# forcefoot.net
KiCad netlist of a schematic drawn in EAGLE
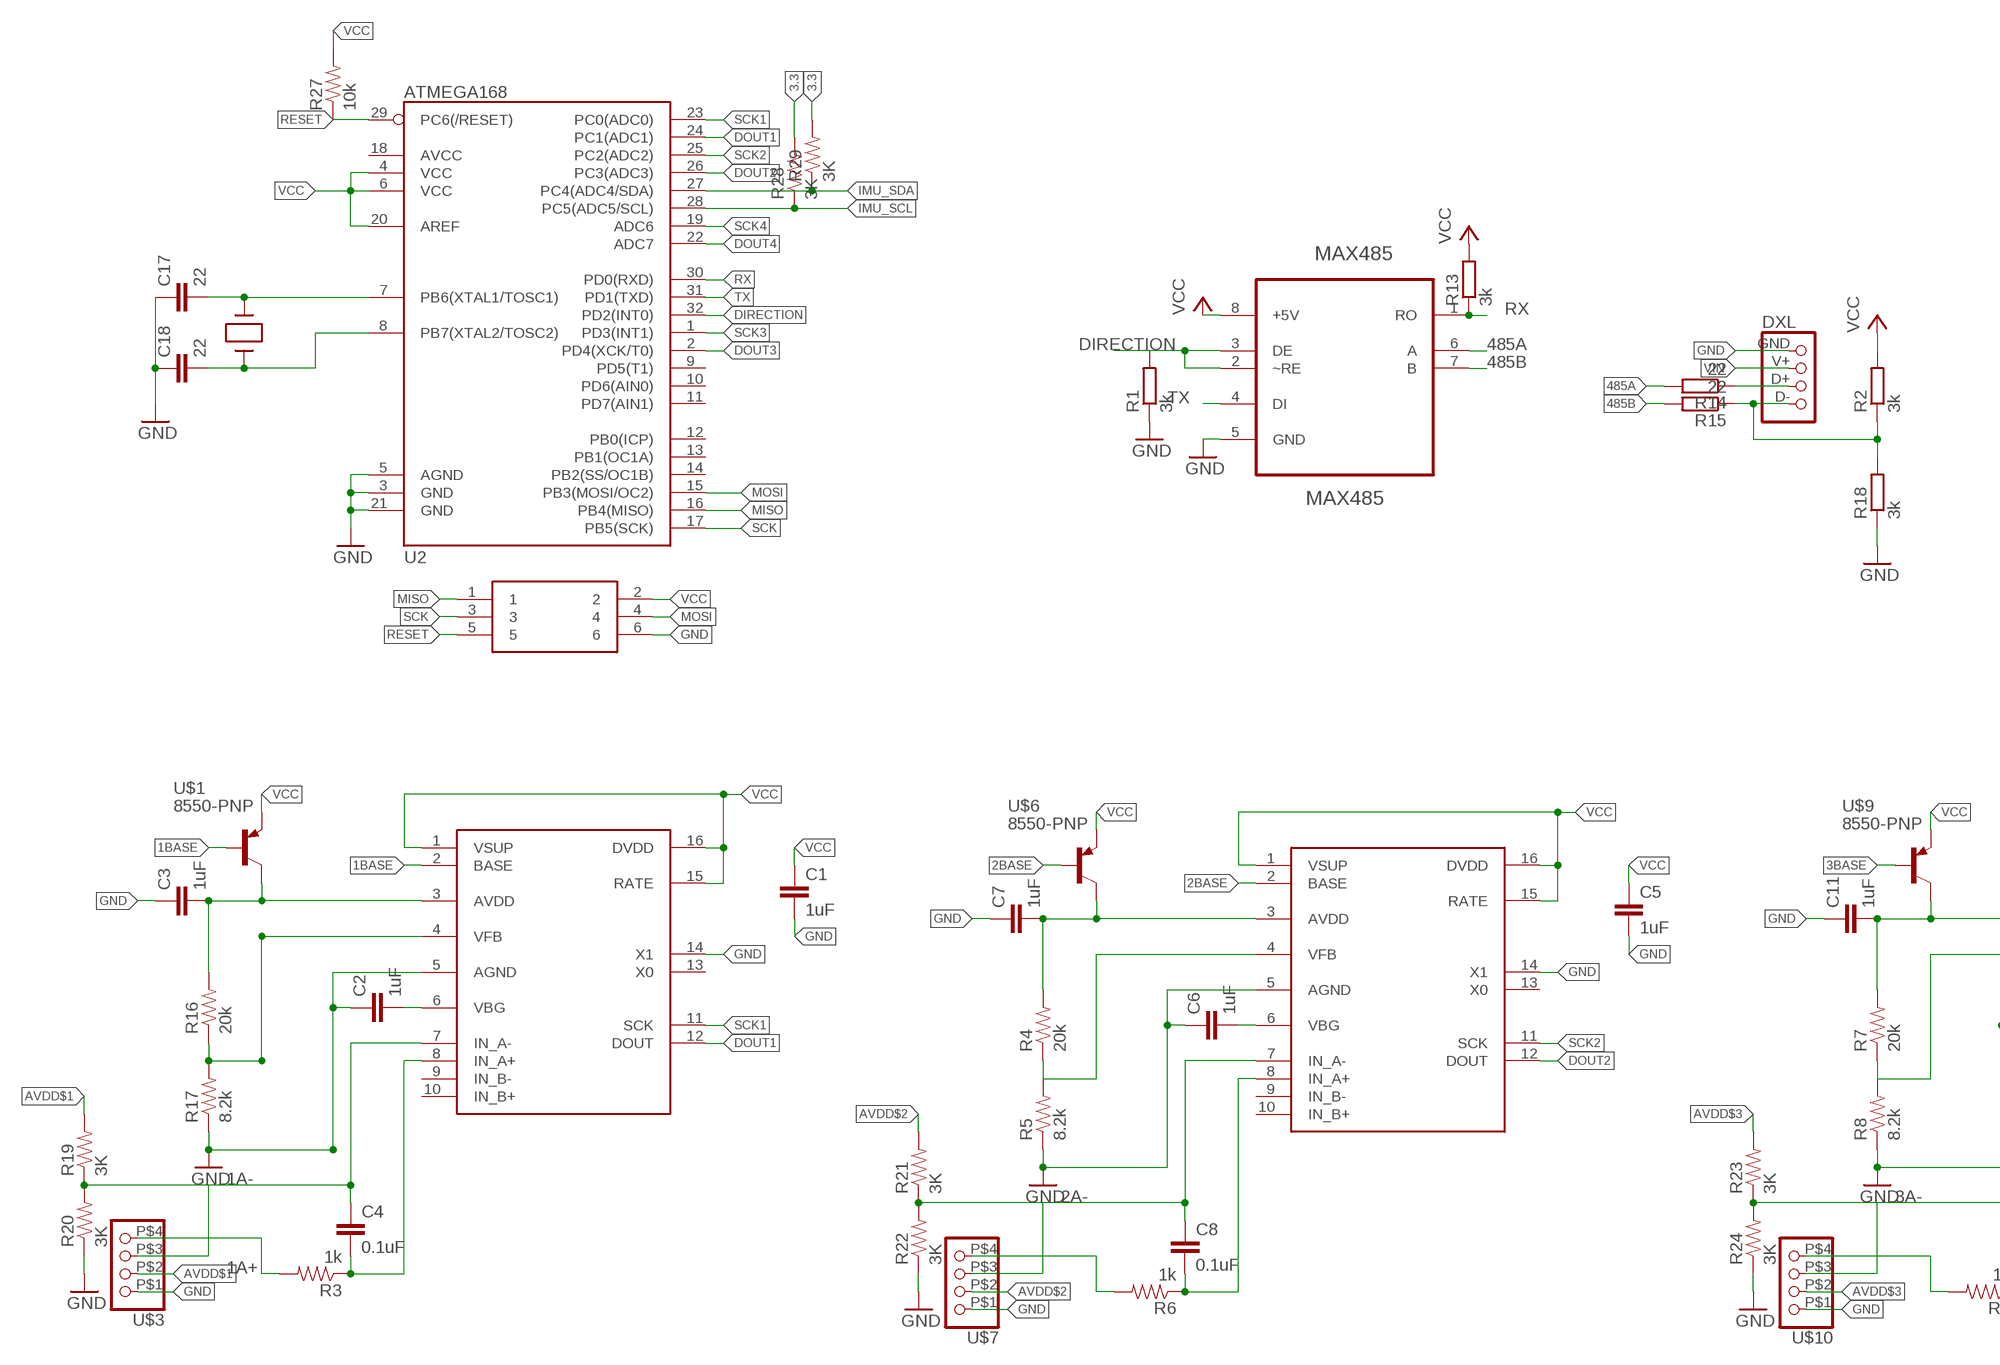
[diagram p0: schematic, sheet 1, part 1 of 2]
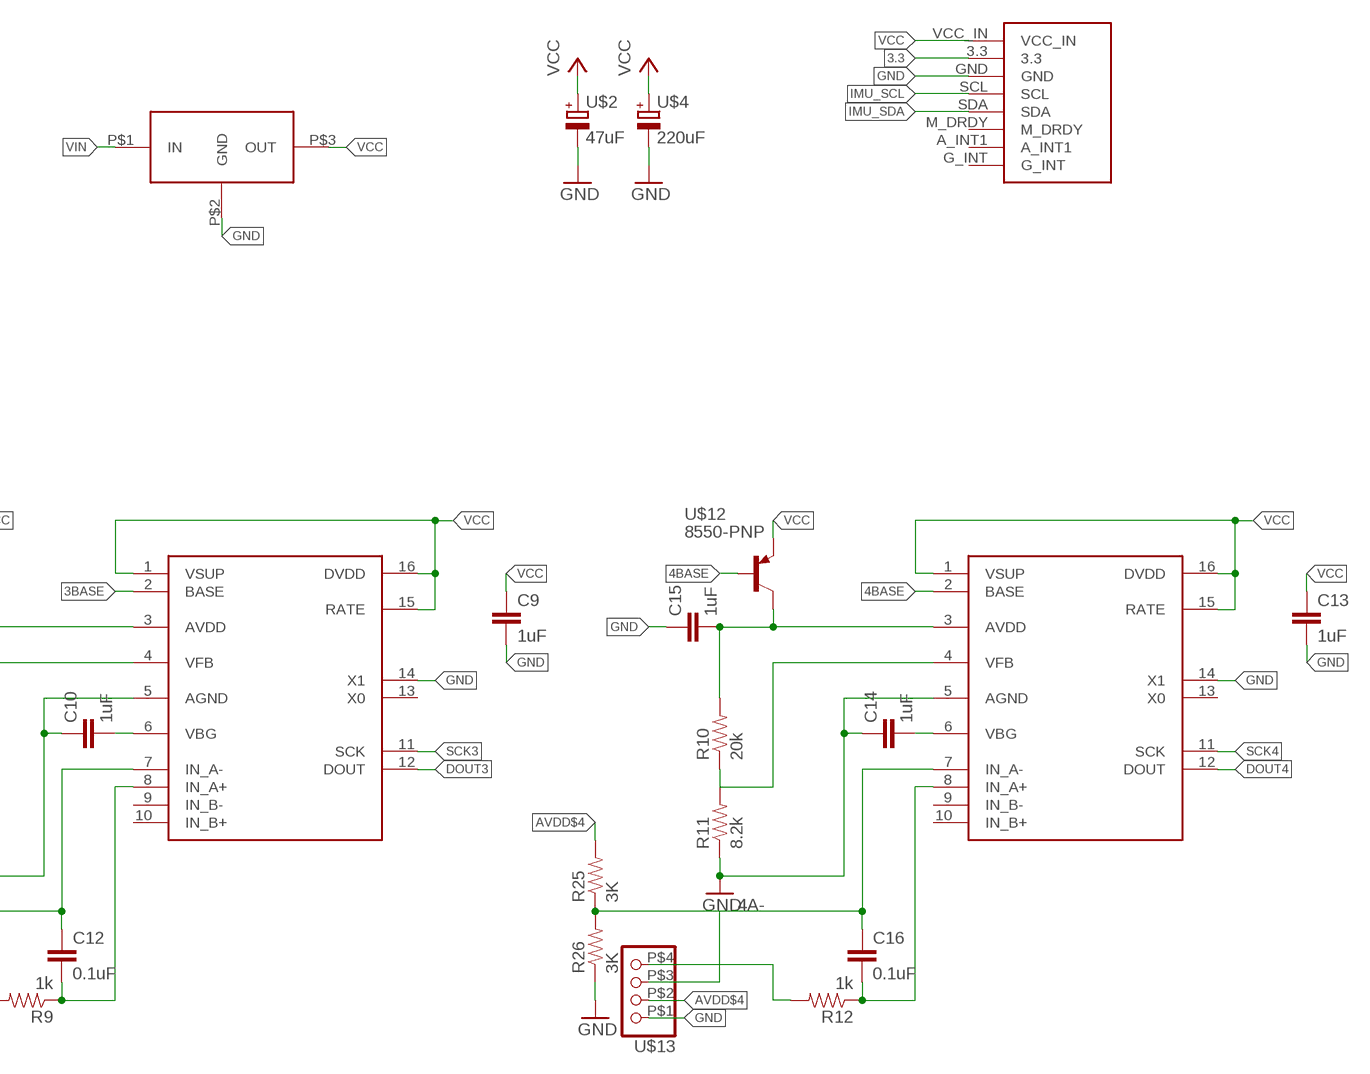
[diagram p1: schematic, sheet 1, part 2 of 2]

(export (version "E")
  (design (tool "Eeschema 10.0.6"))
  (components
    (comp (ref "C1")
      (value "1uF")
      (footprint "eagle-import:0805")
      (libsource (lib "eagle-import") (part "CAP0805"))
    )
    (comp (ref "C2")
      (value "1uF")
      (footprint "eagle-import:0805")
      (libsource (lib "eagle-import") (part "CAP0805"))
    )
    (comp (ref "C3")
      (value "1uF")
      (footprint "eagle-import:0805")
      (libsource (lib "eagle-import") (part "CAP0805"))
    )
    (comp (ref "C4")
      (value "0.1uF")
      (footprint "eagle-import:0805")
      (libsource (lib "eagle-import") (part "CAP0805"))
    )
    (comp (ref "C5")
      (value "1uF")
      (footprint "eagle-import:0805")
      (libsource (lib "eagle-import") (part "CAP0805"))
    )
    (comp (ref "C6")
      (value "1uF")
      (footprint "eagle-import:0805")
      (libsource (lib "eagle-import") (part "CAP0805"))
    )
    (comp (ref "C7")
      (value "1uF")
      (footprint "eagle-import:0805")
      (libsource (lib "eagle-import") (part "CAP0805"))
    )
    (comp (ref "C8")
      (value "0.1uF")
      (footprint "eagle-import:0805")
      (libsource (lib "eagle-import") (part "CAP0805"))
    )
    (comp (ref "C9")
      (value "1uF")
      (footprint "eagle-import:0805")
      (libsource (lib "eagle-import") (part "CAP0805"))
    )
    (comp (ref "C10")
      (value "1uF")
      (footprint "eagle-import:0805")
      (libsource (lib "eagle-import") (part "CAP0805"))
    )
    (comp (ref "C11")
      (value "1uF")
      (footprint "eagle-import:0805")
      (libsource (lib "eagle-import") (part "CAP0805"))
    )
    (comp (ref "C12")
      (value "0.1uF")
      (footprint "eagle-import:0805")
      (libsource (lib "eagle-import") (part "CAP0805"))
    )
    (comp (ref "C13")
      (value "1uF")
      (footprint "eagle-import:0805")
      (libsource (lib "eagle-import") (part "CAP0805"))
    )
    (comp (ref "C14")
      (value "1uF")
      (footprint "eagle-import:0805")
      (libsource (lib "eagle-import") (part "CAP0805"))
    )
    (comp (ref "C15")
      (value "1uF")
      (footprint "eagle-import:0805")
      (libsource (lib "eagle-import") (part "CAP0805"))
    )
    (comp (ref "C16")
      (value "0.1uF")
      (footprint "eagle-import:0805")
      (libsource (lib "eagle-import") (part "CAP0805"))
    )
    (comp (ref "C17")
      (value "22")
      (footprint "eagle-import:C0603")
      (libsource (lib "eagle-import") (part "C_EU_22PF"))
    )
    (comp (ref "C18")
      (value "22")
      (footprint "eagle-import:C0603")
      (libsource (lib "eagle-import") (part "C_EU_22PF"))
    )
    (comp (ref "DXL")
      (value "CONNEC_1X04_485")
      (footprint "eagle-import:CONNEC_485")
      (libsource (lib "eagle-import") (part "CONNEC_1X04_485"))
    )
    (comp (ref "HX1")
      (value "HX711SO16")
      (footprint "eagle-import:SO16")
      (libsource (lib "eagle-import") (part "HX711SO16"))
    )
    (comp (ref "HX2")
      (value "HX711SO16")
      (footprint "eagle-import:SO16")
      (libsource (lib "eagle-import") (part "HX711SO16"))
    )
    (comp (ref "HX3")
      (value "HX711SO16")
      (footprint "eagle-import:SO16")
      (libsource (lib "eagle-import") (part "HX711SO16"))
    )
    (comp (ref "HX4")
      (value "HX711SO16")
      (footprint "eagle-import:SO16")
      (libsource (lib "eagle-import") (part "HX711SO16"))
    )
    (comp (ref "IMU")
      (value "GY-85")
      (footprint "eagle-import:GY-85")
      (libsource (lib "eagle-import") (part "GY-85"))
    )
    (comp (ref "ISP")
      (value "CONNEC_2X03")
      (footprint "eagle-import:CONNEC_2X03")
      (libsource (lib "eagle-import") (part "CONNEC_2X03"))
    )
    (comp (ref "MAX485")
      (value "MAX485")
      (footprint "eagle-import:SO8")
      (fields (field (name "MPN") "MAX485EESA+"))
      (libsource (lib "eagle-import") (part "MAX485"))
    )
    (comp (ref "R1")
      (value "3k")
      (footprint "eagle-import:R0805")
      (libsource (lib "eagle-import") (part "RESISTANCE-R0805"))
    )
    (comp (ref "R2")
      (value "3k")
      (footprint "eagle-import:R0805")
      (libsource (lib "eagle-import") (part "RESISTANCE-R0805"))
    )
    (comp (ref "R3")
      (value "1k")
      (footprint "eagle-import:0805")
      (libsource (lib "eagle-import") (part "RESISTOR0805-RES"))
    )
    (comp (ref "R4")
      (value "20k")
      (footprint "eagle-import:0805")
      (libsource (lib "eagle-import") (part "RESISTOR0805-RES"))
    )
    (comp (ref "R5")
      (value "8.2k")
      (footprint "eagle-import:0805")
      (libsource (lib "eagle-import") (part "RESISTOR0805-RES"))
    )
    (comp (ref "R6")
      (value "1k")
      (footprint "eagle-import:0805")
      (libsource (lib "eagle-import") (part "RESISTOR0805-RES"))
    )
    (comp (ref "R7")
      (value "20k")
      (footprint "eagle-import:0805")
      (libsource (lib "eagle-import") (part "RESISTOR0805-RES"))
    )
    (comp (ref "R8")
      (value "8.2k")
      (footprint "eagle-import:0805")
      (libsource (lib "eagle-import") (part "RESISTOR0805-RES"))
    )
    (comp (ref "R9")
      (value "1k")
      (footprint "eagle-import:0805")
      (libsource (lib "eagle-import") (part "RESISTOR0805-RES"))
    )
    (comp (ref "R10")
      (value "20k")
      (footprint "eagle-import:0805")
      (libsource (lib "eagle-import") (part "RESISTOR0805-RES"))
    )
    (comp (ref "R11")
      (value "8.2k")
      (footprint "eagle-import:0805")
      (libsource (lib "eagle-import") (part "RESISTOR0805-RES"))
    )
    (comp (ref "R12")
      (value "1k")
      (footprint "eagle-import:0805")
      (libsource (lib "eagle-import") (part "RESISTOR0805-RES"))
    )
    (comp (ref "R13")
      (value "3k")
      (footprint "eagle-import:R0805")
      (libsource (lib "eagle-import") (part "RESISTANCE-R0805"))
    )
    (comp (ref "R14")
      (value "22")
      (footprint "eagle-import:R0805")
      (libsource (lib "eagle-import") (part "RESISTANCE-R0805"))
    )
    (comp (ref "R15")
      (value "22")
      (footprint "eagle-import:R0805")
      (libsource (lib "eagle-import") (part "RESISTANCE-R0805"))
    )
    (comp (ref "R16")
      (value "20k")
      (footprint "eagle-import:0805")
      (libsource (lib "eagle-import") (part "RESISTOR0805-RES"))
    )
    (comp (ref "R17")
      (value "8.2k")
      (footprint "eagle-import:0805")
      (libsource (lib "eagle-import") (part "RESISTOR0805-RES"))
    )
    (comp (ref "R18")
      (value "3k")
      (footprint "eagle-import:R0805")
      (libsource (lib "eagle-import") (part "RESISTANCE-R0805"))
    )
    (comp (ref "R19")
      (value "3K")
      (footprint "eagle-import:0805")
      (libsource (lib "eagle-import") (part "RESISTOR0805-RES"))
    )
    (comp (ref "R20")
      (value "3K")
      (footprint "eagle-import:0805")
      (libsource (lib "eagle-import") (part "RESISTOR0805-RES"))
    )
    (comp (ref "R21")
      (value "3K")
      (footprint "eagle-import:0805")
      (libsource (lib "eagle-import") (part "RESISTOR0805-RES"))
    )
    (comp (ref "R22")
      (value "3K")
      (footprint "eagle-import:0805")
      (libsource (lib "eagle-import") (part "RESISTOR0805-RES"))
    )
    (comp (ref "R23")
      (value "3K")
      (footprint "eagle-import:0805")
      (libsource (lib "eagle-import") (part "RESISTOR0805-RES"))
    )
    (comp (ref "R24")
      (value "3K")
      (footprint "eagle-import:0805")
      (libsource (lib "eagle-import") (part "RESISTOR0805-RES"))
    )
    (comp (ref "R25")
      (value "3K")
      (footprint "eagle-import:0805")
      (libsource (lib "eagle-import") (part "RESISTOR0805-RES"))
    )
    (comp (ref "R26")
      (value "3K")
      (footprint "eagle-import:0805")
      (libsource (lib "eagle-import") (part "RESISTOR0805-RES"))
    )
    (comp (ref "R27")
      (value "10k")
      (footprint "eagle-import:0805")
      (libsource (lib "eagle-import") (part "RESISTOR0805-RES"))
    )
    (comp (ref "R28")
      (value "3K")
      (footprint "eagle-import:0805")
      (libsource (lib "eagle-import") (part "RESISTOR0805-RES"))
    )
    (comp (ref "R29")
      (value "3K")
      (footprint "eagle-import:0805")
      (libsource (lib "eagle-import") (part "RESISTOR0805-RES"))
    )
    (comp (ref "REG")
      (value "REG_5V")
      (footprint "eagle-import:TRACOPOWER")
      (libsource (lib "eagle-import") (part "REG_5V"))
    )
    (comp (ref "U$1")
      (value "8550-PNP")
      (footprint "eagle-import:SOT-23")
      (libsource (lib "eagle-import") (part "8550-PNP"))
    )
    (comp (ref "U$2")
      (value "47uF")
      (footprint "eagle-import:PANASONIC_D")
      (libsource (lib "eagle-import") (part "CPOL_EUPANASONIC_D"))
    )
    (comp (ref "U$3")
      (value "CONNEC_1X041.5")
      (footprint "eagle-import:4P1.5")
      (libsource (lib "eagle-import") (part "CONNEC_1X041.5"))
    )
    (comp (ref "U$4")
      (value "220uF")
      (footprint "eagle-import:PANASONIC_D8")
      (libsource (lib "eagle-import") (part "CPOL_EUPANASONIC_D8"))
    )
    (comp (ref "U$6")
      (value "8550-PNP")
      (footprint "eagle-import:SOT-23")
      (libsource (lib "eagle-import") (part "8550-PNP"))
    )
    (comp (ref "U$7")
      (value "CONNEC_1X041.5")
      (footprint "eagle-import:4P1.5")
      (libsource (lib "eagle-import") (part "CONNEC_1X041.5"))
    )
    (comp (ref "U$9")
      (value "8550-PNP")
      (footprint "eagle-import:SOT-23")
      (libsource (lib "eagle-import") (part "8550-PNP"))
    )
    (comp (ref "U$10")
      (value "CONNEC_1X041.5")
      (footprint "eagle-import:4P1.5")
      (libsource (lib "eagle-import") (part "CONNEC_1X041.5"))
    )
    (comp (ref "U$12")
      (value "8550-PNP")
      (footprint "eagle-import:SOT-23")
      (libsource (lib "eagle-import") (part "8550-PNP"))
    )
    (comp (ref "U$13")
      (value "CONNEC_1X041.5")
      (footprint "eagle-import:4P1.5")
      (libsource (lib "eagle-import") (part "CONNEC_1X041.5"))
    )
    (comp (ref "U2")
      (value "ATMEGA168")
      (footprint "eagle-import:TQFP32-08")
      (libsource (lib "eagle-import") (part "ATMEGA168"))
    )
    (comp (ref "XTAL1")
      (value "QUARTZ")
      (footprint "eagle-import:HC49US")
      (libsource (lib "eagle-import") (part "QUARTZ"))
    )
  )
  (nets
    (net (code "1") (name "/1A+") (class "Default")
      (node (ref "R3") (pin "2") (pinfunction "2_2") (pintype "passive"))
      (node (ref "U$3") (pin "P$4") (pinfunction "4_P$4") (pintype "passive"))
    )
    (net (code "2") (name "/1A-") (class "Default")
      (node (ref "C4") (pin "1") (pinfunction "1_1") (pintype "passive"))
      (node (ref "HX1") (pin "7") (pinfunction "IN_A-_7") (pintype "bidirectional"))
      (node (ref "R19") (pin "1") (pinfunction "1_1") (pintype "passive"))
      (node (ref "R20") (pin "2") (pinfunction "2_2") (pintype "passive"))
      (node (ref "U$3") (pin "P$3") (pinfunction "3_P$3") (pintype "passive"))
    )
    (net (code "3") (name "/2A-") (class "Default")
      (node (ref "C8") (pin "1") (pinfunction "1_1") (pintype "passive"))
      (node (ref "HX2") (pin "7") (pinfunction "IN_A-_7") (pintype "bidirectional"))
      (node (ref "R21") (pin "1") (pinfunction "1_1") (pintype "passive"))
      (node (ref "R22") (pin "2") (pinfunction "2_2") (pintype "passive"))
      (node (ref "U$7") (pin "P$3") (pinfunction "3_P$3") (pintype "passive"))
    )
    (net (code "4") (name "/3A-") (class "Default")
      (node (ref "C12") (pin "1") (pinfunction "1_1") (pintype "passive"))
      (node (ref "HX3") (pin "7") (pinfunction "IN_A-_7") (pintype "bidirectional"))
      (node (ref "R23") (pin "1") (pinfunction "1_1") (pintype "passive"))
      (node (ref "R24") (pin "2") (pinfunction "2_2") (pintype "passive"))
      (node (ref "U$10") (pin "P$3") (pinfunction "3_P$3") (pintype "passive"))
    )
    (net (code "5") (name "/4A-") (class "Default")
      (node (ref "C16") (pin "1") (pinfunction "1_1") (pintype "passive"))
      (node (ref "HX4") (pin "7") (pinfunction "IN_A-_7") (pintype "bidirectional"))
      (node (ref "R25") (pin "1") (pinfunction "1_1") (pintype "passive"))
      (node (ref "R26") (pin "2") (pinfunction "2_2") (pintype "passive"))
      (node (ref "U$13") (pin "P$3") (pinfunction "3_P$3") (pintype "passive"))
    )
    (net (code "6") (name "1BASE") (class "Default")
      (node (ref "HX1") (pin "2") (pinfunction "BASE_2") (pintype "bidirectional"))
      (node (ref "U$1") (pin "1") (pinfunction "B_1") (pintype "passive"))
    )
    (net (code "7") (name "2BASE") (class "Default")
      (node (ref "HX2") (pin "2") (pinfunction "BASE_2") (pintype "bidirectional"))
      (node (ref "U$6") (pin "1") (pinfunction "B_1") (pintype "passive"))
    )
    (net (code "8") (name "3.3") (class "Default")
      (node (ref "IMU") (pin "3.3") (pinfunction "3.3_3.3") (pintype "bidirectional"))
      (node (ref "R28") (pin "2") (pinfunction "2_2") (pintype "passive"))
      (node (ref "R29") (pin "2") (pinfunction "2_2") (pintype "passive"))
    )
    (net (code "9") (name "3BASE") (class "Default")
      (node (ref "HX3") (pin "2") (pinfunction "BASE_2") (pintype "bidirectional"))
      (node (ref "U$9") (pin "1") (pinfunction "B_1") (pintype "passive"))
    )
    (net (code "10") (name "4BASE") (class "Default")
      (node (ref "HX4") (pin "2") (pinfunction "BASE_2") (pintype "bidirectional"))
      (node (ref "U$12") (pin "1") (pinfunction "B_1") (pintype "passive"))
    )
    (net (code "11") (name "485A") (class "Default")
      (node (ref "MAX485") (pin "6") (pinfunction "A_6") (pintype "bidirectional"))
      (node (ref "R14") (pin "2") (pinfunction "2_2") (pintype "passive"))
    )
    (net (code "12") (name "485B") (class "Default")
      (node (ref "MAX485") (pin "7") (pinfunction "B_7") (pintype "bidirectional"))
      (node (ref "R15") (pin "2") (pinfunction "2_2") (pintype "passive"))
    )
    (net (code "13") (name "AVDD$1") (class "Default")
      (node (ref "C3") (pin "2") (pinfunction "2_2") (pintype "passive"))
      (node (ref "HX1") (pin "3") (pinfunction "AVDD_3") (pintype "bidirectional"))
      (node (ref "R16") (pin "2") (pinfunction "2_2") (pintype "passive"))
      (node (ref "R19") (pin "2") (pinfunction "2_2") (pintype "passive"))
      (node (ref "U$1") (pin "3") (pinfunction "C_3") (pintype "passive"))
      (node (ref "U$3") (pin "P$2") (pinfunction "2_P$2") (pintype "passive"))
    )
    (net (code "14") (name "AVDD$2") (class "Default")
      (node (ref "C7") (pin "2") (pinfunction "2_2") (pintype "passive"))
      (node (ref "HX2") (pin "3") (pinfunction "AVDD_3") (pintype "bidirectional"))
      (node (ref "R21") (pin "2") (pinfunction "2_2") (pintype "passive"))
      (node (ref "R4") (pin "2") (pinfunction "2_2") (pintype "passive"))
      (node (ref "U$6") (pin "3") (pinfunction "C_3") (pintype "passive"))
      (node (ref "U$7") (pin "P$2") (pinfunction "2_P$2") (pintype "passive"))
    )
    (net (code "15") (name "AVDD$3") (class "Default")
      (node (ref "C11") (pin "2") (pinfunction "2_2") (pintype "passive"))
      (node (ref "HX3") (pin "3") (pinfunction "AVDD_3") (pintype "bidirectional"))
      (node (ref "R23") (pin "2") (pinfunction "2_2") (pintype "passive"))
      (node (ref "R7") (pin "2") (pinfunction "2_2") (pintype "passive"))
      (node (ref "U$10") (pin "P$2") (pinfunction "2_P$2") (pintype "passive"))
      (node (ref "U$9") (pin "3") (pinfunction "C_3") (pintype "passive"))
    )
    (net (code "16") (name "AVDD$4") (class "Default")
      (node (ref "C15") (pin "2") (pinfunction "2_2") (pintype "passive"))
      (node (ref "HX4") (pin "3") (pinfunction "AVDD_3") (pintype "bidirectional"))
      (node (ref "R10") (pin "2") (pinfunction "2_2") (pintype "passive"))
      (node (ref "R25") (pin "2") (pinfunction "2_2") (pintype "passive"))
      (node (ref "U$12") (pin "3") (pinfunction "C_3") (pintype "passive"))
      (node (ref "U$13") (pin "P$2") (pinfunction "2_P$2") (pintype "passive"))
    )
    (net (code "17") (name "DIRECTION") (class "Default")
      (node (ref "MAX485") (pin "2") (pinfunction "~{RE}_2") (pintype "input"))
      (node (ref "MAX485") (pin "3") (pinfunction "DE_3") (pintype "input"))
      (node (ref "R1") (pin "2") (pinfunction "2_2") (pintype "passive"))
      (node (ref "U2") (pin "32") (pinfunction "PD2(INT0)_32") (pintype "bidirectional"))
    )
    (net (code "18") (name "DOUT1") (class "Default")
      (node (ref "HX1") (pin "12") (pinfunction "DOUT_12") (pintype "bidirectional"))
      (node (ref "U2") (pin "24") (pinfunction "PC1(ADC1)_24") (pintype "bidirectional"))
    )
    (net (code "19") (name "DOUT2") (class "Default")
      (node (ref "HX2") (pin "12") (pinfunction "DOUT_12") (pintype "bidirectional"))
      (node (ref "U2") (pin "26") (pinfunction "PC3(ADC3)_26") (pintype "bidirectional"))
    )
    (net (code "20") (name "DOUT3") (class "Default")
      (node (ref "HX3") (pin "12") (pinfunction "DOUT_12") (pintype "bidirectional"))
      (node (ref "U2") (pin "2") (pinfunction "PD4(XCK/T0)_2") (pintype "bidirectional"))
    )
    (net (code "21") (name "DOUT4") (class "Default")
      (node (ref "HX4") (pin "12") (pinfunction "DOUT_12") (pintype "bidirectional"))
      (node (ref "U2") (pin "22") (pinfunction "ADC7_22") (pintype "bidirectional"))
    )
    (net (code "22") (name "GND") (class "Default")
      (node (ref "C1") (pin "2") (pinfunction "2_2") (pintype "passive"))
      (node (ref "C10") (pin "1") (pinfunction "1_1") (pintype "passive"))
      (node (ref "C11") (pin "1") (pinfunction "1_1") (pintype "passive"))
      (node (ref "C13") (pin "2") (pinfunction "2_2") (pintype "passive"))
      (node (ref "C14") (pin "1") (pinfunction "1_1") (pintype "passive"))
      (node (ref "C15") (pin "1") (pinfunction "1_1") (pintype "passive"))
      (node (ref "C17") (pin "1") (pinfunction "1_1") (pintype "passive"))
      (node (ref "C18") (pin "1") (pinfunction "1_1") (pintype "passive"))
      (node (ref "C2") (pin "1") (pinfunction "1_1") (pintype "passive"))
      (node (ref "C3") (pin "1") (pinfunction "1_1") (pintype "passive"))
      (node (ref "C5") (pin "2") (pinfunction "2_2") (pintype "passive"))
      (node (ref "C6") (pin "1") (pinfunction "1_1") (pintype "passive"))
      (node (ref "C7") (pin "1") (pinfunction "1_1") (pintype "passive"))
      (node (ref "C9") (pin "2") (pinfunction "2_2") (pintype "passive"))
      (node (ref "DXL") (pin "GND") (pinfunction "1_GND") (pintype "passive"))
      (node (ref "HX1") (pin "14") (pinfunction "X1_14") (pintype "bidirectional"))
      (node (ref "HX1") (pin "5") (pinfunction "AGND_5") (pintype "bidirectional"))
      (node (ref "HX2") (pin "14") (pinfunction "X1_14") (pintype "bidirectional"))
      (node (ref "HX2") (pin "5") (pinfunction "AGND_5") (pintype "bidirectional"))
      (node (ref "HX3") (pin "14") (pinfunction "X1_14") (pintype "bidirectional"))
      (node (ref "HX3") (pin "5") (pinfunction "AGND_5") (pintype "bidirectional"))
      (node (ref "HX4") (pin "14") (pinfunction "X1_14") (pintype "bidirectional"))
      (node (ref "HX4") (pin "5") (pinfunction "AGND_5") (pintype "bidirectional"))
      (node (ref "IMU") (pin "GND") (pinfunction "GND_GND") (pintype "bidirectional"))
      (node (ref "ISP") (pin "6") (pinfunction "6_6") (pintype "bidirectional"))
      (node (ref "MAX485") (pin "5") (pinfunction "GND_5") (pintype "passive"))
      (node (ref "R1") (pin "1") (pinfunction "1_1") (pintype "passive"))
      (node (ref "R11") (pin "1") (pinfunction "1_1") (pintype "passive"))
      (node (ref "R17") (pin "1") (pinfunction "1_1") (pintype "passive"))
      (node (ref "R18") (pin "1") (pinfunction "1_1") (pintype "passive"))
      (node (ref "R20") (pin "1") (pinfunction "1_1") (pintype "passive"))
      (node (ref "R22") (pin "1") (pinfunction "1_1") (pintype "passive"))
      (node (ref "R24") (pin "1") (pinfunction "1_1") (pintype "passive"))
      (node (ref "R26") (pin "1") (pinfunction "1_1") (pintype "passive"))
      (node (ref "R5") (pin "1") (pinfunction "1_1") (pintype "passive"))
      (node (ref "R8") (pin "1") (pinfunction "1_1") (pintype "passive"))
      (node (ref "REG") (pin "P$2") (pinfunction "GND_P$2") (pintype "bidirectional"))
      (node (ref "U$10") (pin "P$1") (pinfunction "1_P$1") (pintype "passive"))
      (node (ref "U$13") (pin "P$1") (pinfunction "1_P$1") (pintype "passive"))
      (node (ref "U$2") (pin "-") (pinfunction "-_-") (pintype "passive"))
      (node (ref "U$3") (pin "P$1") (pinfunction "1_P$1") (pintype "passive"))
      (node (ref "U$4") (pin "-") (pinfunction "-_-") (pintype "passive"))
      (node (ref "U$7") (pin "P$1") (pinfunction "1_P$1") (pintype "passive"))
      (node (ref "U2") (pin "21") (pinfunction "GND_21") (pintype "bidirectional"))
      (node (ref "U2") (pin "3") (pinfunction "GND_3") (pintype "bidirectional"))
      (node (ref "U2") (pin "5") (pinfunction "AGND_5") (pintype "bidirectional"))
    )
    (net (code "23") (name "IMU_SCL") (class "Default")
      (node (ref "IMU") (pin "SCL") (pinfunction "SCL_SCL") (pintype "bidirectional"))
      (node (ref "R28") (pin "1") (pinfunction "1_1") (pintype "passive"))
      (node (ref "U2") (pin "28") (pinfunction "PC5(ADC5/SCL)_28") (pintype "bidirectional"))
    )
    (net (code "24") (name "IMU_SDA") (class "Default")
      (node (ref "IMU") (pin "SDA") (pinfunction "SDA_SDA") (pintype "bidirectional"))
      (node (ref "R29") (pin "1") (pinfunction "1_1") (pintype "passive"))
      (node (ref "U2") (pin "27") (pinfunction "PC4(ADC4/SDA)_27") (pintype "bidirectional"))
    )
    (net (code "25") (name "MISO") (class "Default")
      (node (ref "ISP") (pin "1") (pinfunction "1_1") (pintype "bidirectional"))
      (node (ref "U2") (pin "16") (pinfunction "PB4(MISO)_16") (pintype "bidirectional"))
    )
    (net (code "26") (name "MOSI") (class "Default")
      (node (ref "ISP") (pin "4") (pinfunction "4_4") (pintype "bidirectional"))
      (node (ref "U2") (pin "15") (pinfunction "PB3(MOSI/OC2)_15") (pintype "bidirectional"))
    )
    (net (code "27") (name "Net-(DXL-3)") (class "Default")
      (node (ref "DXL") (pin "D+") (pinfunction "3_D+") (pintype "passive"))
      (node (ref "R14") (pin "1") (pinfunction "1_1") (pintype "passive"))
    )
    (net (code "28") (name "Net-(DXL-4)") (class "Default")
      (node (ref "DXL") (pin "D-") (pinfunction "4_D-") (pintype "passive"))
      (node (ref "R15") (pin "1") (pinfunction "1_1") (pintype "passive"))
      (node (ref "R18") (pin "2") (pinfunction "2_2") (pintype "passive"))
      (node (ref "R2") (pin "1") (pinfunction "1_1") (pintype "passive"))
    )
    (net (code "29") (name "Net-(HX1-IN_A+)") (class "Default")
      (node (ref "C4") (pin "2") (pinfunction "2_2") (pintype "passive"))
      (node (ref "HX1") (pin "8") (pinfunction "IN_A+_8") (pintype "bidirectional"))
      (node (ref "R3") (pin "1") (pinfunction "1_1") (pintype "passive"))
    )
    (net (code "30") (name "Net-(HX1-VBG)") (class "Default")
      (node (ref "C2") (pin "2") (pinfunction "2_2") (pintype "passive"))
      (node (ref "HX1") (pin "6") (pinfunction "VBG_6") (pintype "bidirectional"))
    )
    (net (code "31") (name "Net-(HX1-VFB)") (class "Default")
      (node (ref "HX1") (pin "4") (pinfunction "VFB_4") (pintype "bidirectional"))
      (node (ref "R16") (pin "1") (pinfunction "1_1") (pintype "passive"))
      (node (ref "R17") (pin "2") (pinfunction "2_2") (pintype "passive"))
    )
    (net (code "32") (name "Net-(HX2-IN_A+)") (class "Default")
      (node (ref "C8") (pin "2") (pinfunction "2_2") (pintype "passive"))
      (node (ref "HX2") (pin "8") (pinfunction "IN_A+_8") (pintype "bidirectional"))
      (node (ref "R6") (pin "1") (pinfunction "1_1") (pintype "passive"))
    )
    (net (code "33") (name "Net-(HX2-VBG)") (class "Default")
      (node (ref "C6") (pin "2") (pinfunction "2_2") (pintype "passive"))
      (node (ref "HX2") (pin "6") (pinfunction "VBG_6") (pintype "bidirectional"))
    )
    (net (code "34") (name "Net-(HX2-VFB)") (class "Default")
      (node (ref "HX2") (pin "4") (pinfunction "VFB_4") (pintype "bidirectional"))
      (node (ref "R4") (pin "1") (pinfunction "1_1") (pintype "passive"))
      (node (ref "R5") (pin "2") (pinfunction "2_2") (pintype "passive"))
    )
    (net (code "35") (name "Net-(HX3-IN_A+)") (class "Default")
      (node (ref "C12") (pin "2") (pinfunction "2_2") (pintype "passive"))
      (node (ref "HX3") (pin "8") (pinfunction "IN_A+_8") (pintype "bidirectional"))
      (node (ref "R9") (pin "1") (pinfunction "1_1") (pintype "passive"))
    )
    (net (code "36") (name "Net-(HX3-VBG)") (class "Default")
      (node (ref "C10") (pin "2") (pinfunction "2_2") (pintype "passive"))
      (node (ref "HX3") (pin "6") (pinfunction "VBG_6") (pintype "bidirectional"))
    )
    (net (code "37") (name "Net-(HX3-VFB)") (class "Default")
      (node (ref "HX3") (pin "4") (pinfunction "VFB_4") (pintype "bidirectional"))
      (node (ref "R7") (pin "1") (pinfunction "1_1") (pintype "passive"))
      (node (ref "R8") (pin "2") (pinfunction "2_2") (pintype "passive"))
    )
    (net (code "38") (name "Net-(HX4-IN_A+)") (class "Default")
      (node (ref "C16") (pin "2") (pinfunction "2_2") (pintype "passive"))
      (node (ref "HX4") (pin "8") (pinfunction "IN_A+_8") (pintype "bidirectional"))
      (node (ref "R12") (pin "1") (pinfunction "1_1") (pintype "passive"))
    )
    (net (code "39") (name "Net-(HX4-VBG)") (class "Default")
      (node (ref "C14") (pin "2") (pinfunction "2_2") (pintype "passive"))
      (node (ref "HX4") (pin "6") (pinfunction "VBG_6") (pintype "bidirectional"))
    )
    (net (code "40") (name "Net-(HX4-VFB)") (class "Default")
      (node (ref "HX4") (pin "4") (pinfunction "VFB_4") (pintype "bidirectional"))
      (node (ref "R10") (pin "1") (pinfunction "1_1") (pintype "passive"))
      (node (ref "R11") (pin "2") (pinfunction "2_2") (pintype "passive"))
    )
    (net (code "41") (name "Net-(U$7-4)") (class "Default")
      (node (ref "R6") (pin "2") (pinfunction "2_2") (pintype "passive"))
      (node (ref "U$7") (pin "P$4") (pinfunction "4_P$4") (pintype "passive"))
    )
    (net (code "42") (name "Net-(U$10-4)") (class "Default")
      (node (ref "R9") (pin "2") (pinfunction "2_2") (pintype "passive"))
      (node (ref "U$10") (pin "P$4") (pinfunction "4_P$4") (pintype "passive"))
    )
    (net (code "43") (name "Net-(U$13-4)") (class "Default")
      (node (ref "R12") (pin "2") (pinfunction "2_2") (pintype "passive"))
      (node (ref "U$13") (pin "P$4") (pinfunction "4_P$4") (pintype "passive"))
    )
    (net (code "44") (name "Net-(U2-PB6(XTAL1{slash}TOSC1))") (class "Default")
      (node (ref "C17") (pin "2") (pinfunction "2_2") (pintype "passive"))
      (node (ref "U2") (pin "7") (pinfunction "PB6(XTAL1/TOSC1)_7") (pintype "bidirectional"))
      (node (ref "XTAL1") (pin "2") (pinfunction "2_2") (pintype "bidirectional"))
    )
    (net (code "45") (name "Net-(U2-PB7(XTAL2{slash}TOSC2))") (class "Default")
      (node (ref "C18") (pin "2") (pinfunction "2_2") (pintype "passive"))
      (node (ref "U2") (pin "8") (pinfunction "PB7(XTAL2/TOSC2)_8") (pintype "bidirectional"))
      (node (ref "XTAL1") (pin "1") (pinfunction "1_1") (pintype "bidirectional"))
    )
    (net (code "46") (name "RESET") (class "Default")
      (node (ref "ISP") (pin "5") (pinfunction "5_5") (pintype "bidirectional"))
      (node (ref "R27") (pin "1") (pinfunction "1_1") (pintype "passive"))
      (node (ref "U2") (pin "29") (pinfunction "PC6(/RESET)_29") (pintype "bidirectional"))
    )
    (net (code "47") (name "RX") (class "Default")
      (node (ref "MAX485") (pin "1") (pinfunction "RO_1") (pintype "output"))
      (node (ref "R13") (pin "1") (pinfunction "1_1") (pintype "passive"))
      (node (ref "U2") (pin "30") (pinfunction "PD0(RXD)_30") (pintype "bidirectional"))
    )
    (net (code "48") (name "SCK") (class "Default")
      (node (ref "ISP") (pin "3") (pinfunction "3_3") (pintype "bidirectional"))
      (node (ref "U2") (pin "17") (pinfunction "PB5(SCK)_17") (pintype "bidirectional"))
    )
    (net (code "49") (name "SCK1") (class "Default")
      (node (ref "HX1") (pin "11") (pinfunction "SCK_11") (pintype "bidirectional"))
      (node (ref "U2") (pin "23") (pinfunction "PC0(ADC0)_23") (pintype "bidirectional"))
    )
    (net (code "50") (name "SCK2") (class "Default")
      (node (ref "HX2") (pin "11") (pinfunction "SCK_11") (pintype "bidirectional"))
      (node (ref "U2") (pin "25") (pinfunction "PC2(ADC2)_25") (pintype "bidirectional"))
    )
    (net (code "51") (name "SCK3") (class "Default")
      (node (ref "HX3") (pin "11") (pinfunction "SCK_11") (pintype "bidirectional"))
      (node (ref "U2") (pin "1") (pinfunction "PD3(INT1)_1") (pintype "bidirectional"))
    )
    (net (code "52") (name "SCK4") (class "Default")
      (node (ref "HX4") (pin "11") (pinfunction "SCK_11") (pintype "bidirectional"))
      (node (ref "U2") (pin "19") (pinfunction "ADC6_19") (pintype "bidirectional"))
    )
    (net (code "53") (name "TX") (class "Default")
      (node (ref "MAX485") (pin "4") (pinfunction "DI_4") (pintype "input"))
      (node (ref "U2") (pin "31") (pinfunction "PD1(TXD)_31") (pintype "bidirectional"))
    )
    (net (code "54") (name "VCC") (class "Default")
      (node (ref "C1") (pin "1") (pinfunction "1_1") (pintype "passive"))
      (node (ref "C13") (pin "1") (pinfunction "1_1") (pintype "passive"))
      (node (ref "C5") (pin "1") (pinfunction "1_1") (pintype "passive"))
      (node (ref "C9") (pin "1") (pinfunction "1_1") (pintype "passive"))
      (node (ref "HX1") (pin "1") (pinfunction "VSUP_1") (pintype "bidirectional"))
      (node (ref "HX1") (pin "15") (pinfunction "RATE_15") (pintype "bidirectional"))
      (node (ref "HX1") (pin "16") (pinfunction "DVDD_16") (pintype "bidirectional"))
      (node (ref "HX2") (pin "1") (pinfunction "VSUP_1") (pintype "bidirectional"))
      (node (ref "HX2") (pin "15") (pinfunction "RATE_15") (pintype "bidirectional"))
      (node (ref "HX2") (pin "16") (pinfunction "DVDD_16") (pintype "bidirectional"))
      (node (ref "HX3") (pin "1") (pinfunction "VSUP_1") (pintype "bidirectional"))
      (node (ref "HX3") (pin "15") (pinfunction "RATE_15") (pintype "bidirectional"))
      (node (ref "HX3") (pin "16") (pinfunction "DVDD_16") (pintype "bidirectional"))
      (node (ref "HX4") (pin "1") (pinfunction "VSUP_1") (pintype "bidirectional"))
      (node (ref "HX4") (pin "15") (pinfunction "RATE_15") (pintype "bidirectional"))
      (node (ref "HX4") (pin "16") (pinfunction "DVDD_16") (pintype "bidirectional"))
      (node (ref "IMU") (pin "VCC_IN") (pinfunction "VCC_IN_VCC_IN") (pintype "bidirectional"))
      (node (ref "ISP") (pin "2") (pinfunction "2_2") (pintype "bidirectional"))
      (node (ref "MAX485") (pin "8") (pinfunction "+5V_8") (pintype "power_in"))
      (node (ref "R13") (pin "2") (pinfunction "2_2") (pintype "passive"))
      (node (ref "R2") (pin "2") (pinfunction "2_2") (pintype "passive"))
      (node (ref "R27") (pin "2") (pinfunction "2_2") (pintype "passive"))
      (node (ref "REG") (pin "P$3") (pinfunction "OUT_P$3") (pintype "bidirectional"))
      (node (ref "U$1") (pin "2") (pinfunction "E_2") (pintype "passive"))
      (node (ref "U$12") (pin "2") (pinfunction "E_2") (pintype "passive"))
      (node (ref "U$2") (pin "+") (pinfunction "+_+") (pintype "passive"))
      (node (ref "U$4") (pin "+") (pinfunction "+_+") (pintype "passive"))
      (node (ref "U$6") (pin "2") (pinfunction "E_2") (pintype "passive"))
      (node (ref "U$9") (pin "2") (pinfunction "E_2") (pintype "passive"))
      (node (ref "U2") (pin "20") (pinfunction "AREF_20") (pintype "bidirectional"))
      (node (ref "U2") (pin "4") (pinfunction "VCC_4") (pintype "bidirectional"))
      (node (ref "U2") (pin "6") (pinfunction "VCC_6") (pintype "bidirectional"))
    )
    (net (code "55") (name "VIN") (class "Default")
      (node (ref "DXL") (pin "V+") (pinfunction "2_V+") (pintype "passive"))
      (node (ref "REG") (pin "P$1") (pinfunction "IN_P$1") (pintype "bidirectional"))
    )
    (net (code "56") (name "unconnected-(HX1-IN_B+-Pad10)") (class "Default")
      (node (ref "HX1") (pin "10") (pinfunction "IN_B+_10") (pintype "bidirectional"))
    )
    (net (code "57") (name "unconnected-(HX1-IN_B--Pad9)") (class "Default")
      (node (ref "HX1") (pin "9") (pinfunction "IN_B-_9") (pintype "bidirectional"))
    )
    (net (code "58") (name "unconnected-(HX1-X0-Pad13)") (class "Default")
      (node (ref "HX1") (pin "13") (pinfunction "X0_13") (pintype "bidirectional"))
    )
    (net (code "59") (name "unconnected-(HX2-IN_B+-Pad10)") (class "Default")
      (node (ref "HX2") (pin "10") (pinfunction "IN_B+_10") (pintype "bidirectional"))
    )
    (net (code "60") (name "unconnected-(HX2-IN_B--Pad9)") (class "Default")
      (node (ref "HX2") (pin "9") (pinfunction "IN_B-_9") (pintype "bidirectional"))
    )
    (net (code "61") (name "unconnected-(HX2-X0-Pad13)") (class "Default")
      (node (ref "HX2") (pin "13") (pinfunction "X0_13") (pintype "bidirectional"))
    )
    (net (code "62") (name "unconnected-(HX3-IN_B+-Pad10)") (class "Default")
      (node (ref "HX3") (pin "10") (pinfunction "IN_B+_10") (pintype "bidirectional"))
    )
    (net (code "63") (name "unconnected-(HX3-IN_B--Pad9)") (class "Default")
      (node (ref "HX3") (pin "9") (pinfunction "IN_B-_9") (pintype "bidirectional"))
    )
    (net (code "64") (name "unconnected-(HX3-X0-Pad13)") (class "Default")
      (node (ref "HX3") (pin "13") (pinfunction "X0_13") (pintype "bidirectional"))
    )
    (net (code "65") (name "unconnected-(HX4-IN_B+-Pad10)") (class "Default")
      (node (ref "HX4") (pin "10") (pinfunction "IN_B+_10") (pintype "bidirectional"))
    )
    (net (code "66") (name "unconnected-(HX4-IN_B--Pad9)") (class "Default")
      (node (ref "HX4") (pin "9") (pinfunction "IN_B-_9") (pintype "bidirectional"))
    )
    (net (code "67") (name "unconnected-(HX4-X0-Pad13)") (class "Default")
      (node (ref "HX4") (pin "13") (pinfunction "X0_13") (pintype "bidirectional"))
    )
    (net (code "68") (name "unconnected-(IMU-PadA_INT1)") (class "Default")
      (node (ref "IMU") (pin "A_INT1") (pinfunction "A_INT1_A_INT1") (pintype "bidirectional"))
    )
    (net (code "69") (name "unconnected-(IMU-PadG_INT)") (class "Default")
      (node (ref "IMU") (pin "G_INT") (pinfunction "G_INT_G_INT") (pintype "bidirectional"))
    )
    (net (code "70") (name "unconnected-(IMU-PadM_DRDY)") (class "Default")
      (node (ref "IMU") (pin "M_DRDY") (pinfunction "M_DRDY_M_DRDY") (pintype "bidirectional"))
    )
    (net (code "71") (name "unconnected-(U2-AVCC-Pad18)") (class "Default")
      (node (ref "U2") (pin "18") (pinfunction "AVCC_18") (pintype "bidirectional"))
    )
    (net (code "72") (name "unconnected-(U2-PB0(ICP)-Pad12)") (class "Default")
      (node (ref "U2") (pin "12") (pinfunction "PB0(ICP)_12") (pintype "bidirectional"))
    )
    (net (code "73") (name "unconnected-(U2-PB1(OC1A)-Pad13)") (class "Default")
      (node (ref "U2") (pin "13") (pinfunction "PB1(OC1A)_13") (pintype "bidirectional"))
    )
    (net (code "74") (name "unconnected-(U2-PB2(SS{slash}OC1B)-Pad14)") (class "Default")
      (node (ref "U2") (pin "14") (pinfunction "PB2(SS/OC1B)_14") (pintype "bidirectional"))
    )
    (net (code "75") (name "unconnected-(U2-PD5(T1)-Pad9)") (class "Default")
      (node (ref "U2") (pin "9") (pinfunction "PD5(T1)_9") (pintype "bidirectional"))
    )
    (net (code "76") (name "unconnected-(U2-PD6(AIN0)-Pad10)") (class "Default")
      (node (ref "U2") (pin "10") (pinfunction "PD6(AIN0)_10") (pintype "bidirectional"))
    )
    (net (code "77") (name "unconnected-(U2-PD7(AIN1)-Pad11)") (class "Default")
      (node (ref "U2") (pin "11") (pinfunction "PD7(AIN1)_11") (pintype "bidirectional"))
    )
  )
)
